# WIFI_Display.net
KiCad netlist of a schematic drawn in Altium Designer
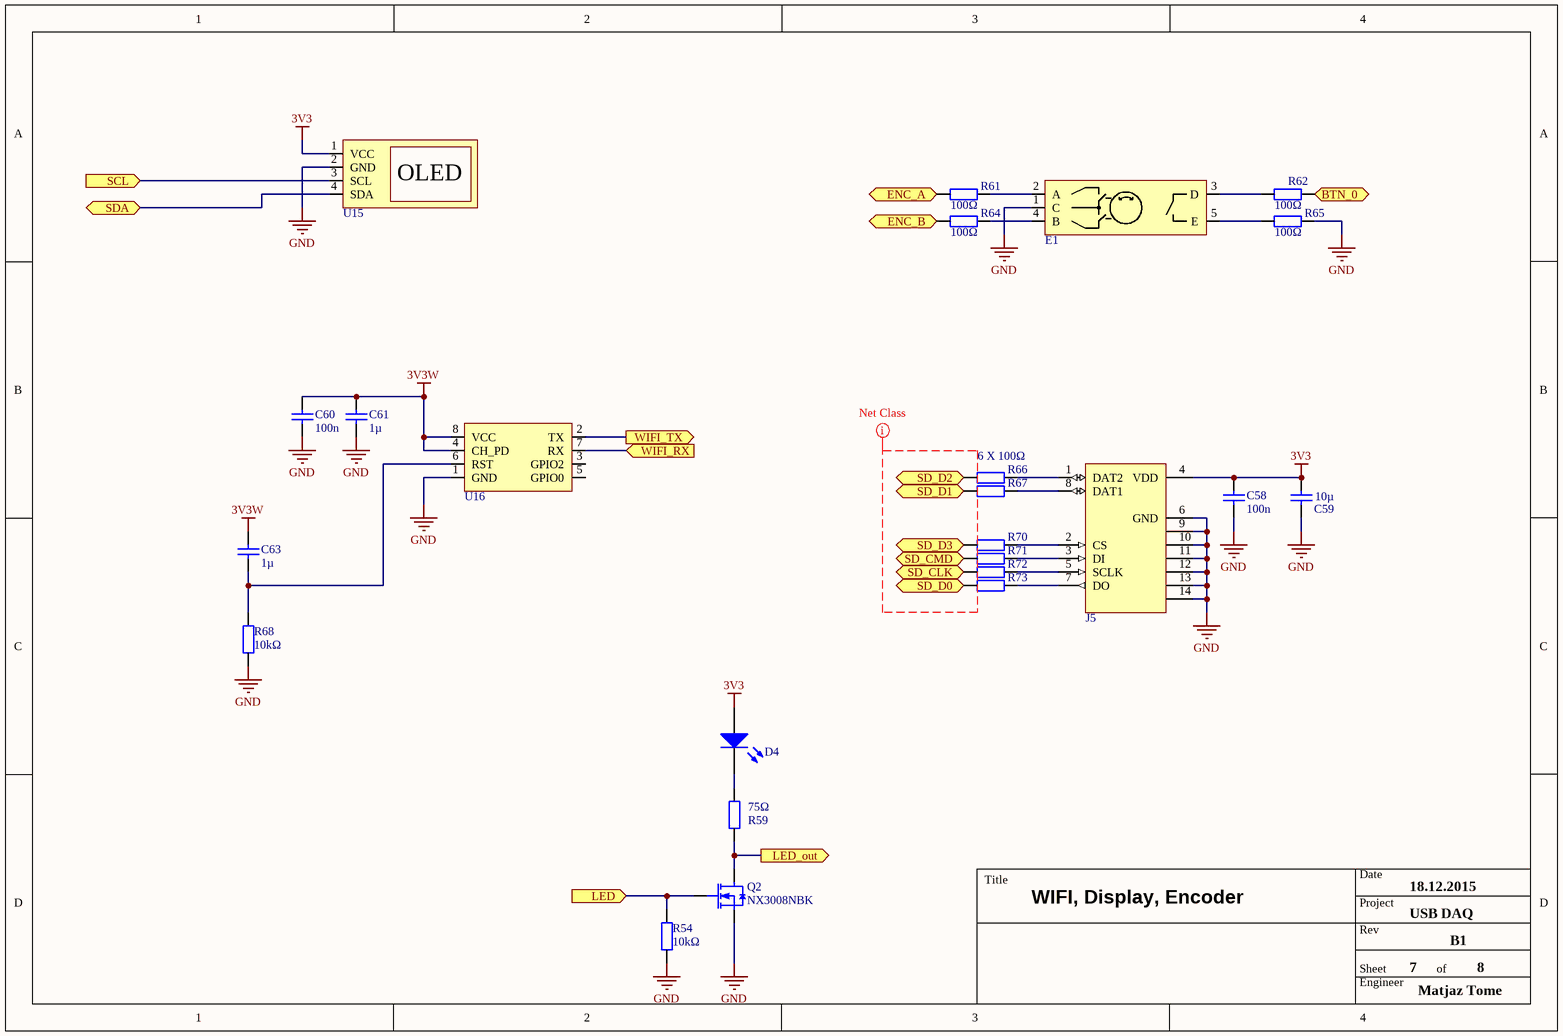
[diagram p0: WIFI_Display.SchDoc]

(export (version "E")
  (design (tool "Eeschema 10.0.6"))
  (components
    (comp (ref "C58")
      (value "100n")
      (footprint "0603C")
      (description "ceramic X7R SMD capacitor smd 0603 100nF 16V")
      (fields (field (name "PART NUMBER") "RSC0013") (field (name "MANUFACTURER") "Murata"))
      (libsource (lib "components") (part "Capacitor"))
    )
    (comp (ref "C59")
      (value "10µ")
      (footprint "0805C")
      (description "ceramic Y5V SMD capacitor smd 0805 10µF 6.3V")
      (fields (field (name "PART NUMBER") "VSC0001") (field (name "MANUFACTURER") "Multicomp"))
      (libsource (lib "components") (part "Capacitor"))
    )
    (comp (ref "C60")
      (value "100n")
      (footprint "0603C")
      (description "ceramic X7R SMD capacitor smd 0603 100nF 16V")
      (fields (field (name "PART NUMBER") "RSC0013") (field (name "MANUFACTURER") "Murata"))
      (libsource (lib "components") (part "Capacitor"))
    )
    (comp (ref "C61")
      (value "1µ")
      (footprint "0603C")
      (description "ceramic X5R SMD capacitor smd 0603 1µF 50V")
      (fields (field (name "PART NUMBER") "ZSC0003") (field (name "MANUFACTURER") "Murata"))
      (libsource (lib "components") (part "Capacitor"))
    )
    (comp (ref "C63")
      (value "1µ")
      (footprint "0603C")
      (description "ceramic X5R SMD capacitor smd 0603 1µF 50V")
      (fields (field (name "PART NUMBER") "ZSC0003") (field (name "MANUFACTURER") "Murata"))
      (libsource (lib "components") (part "Capacitor"))
    )
    (comp (ref "D4")
      (value "KPT-2012SGC")
      (footprint "LED0805")
      (description "Green led SMD 0805")
      (fields (field (name "PART NUMBER") "XXL0000") (field (name "MANUFACTURER") "Kingbright"))
      (libsource (lib "components") (part "LED"))
    )
    (comp (ref "E1")
      (value "EC12D")
      (footprint "EC12D")
      (description "Rotary encoder with push button")
      (fields (field (name "PART NUMBER") "XRE0000") (field (name "MANUFACTURER") "Alps"))
      (libsource (lib "components") (part "ENC1"))
    )
    (comp (ref "J5")
      (value "SD card")
      (footprint "MICRO_SD_AMPHENOL")
      (description "Micro SD card connector")
      (fields (field (name "PART NUMBER") "XMC0000") (field (name "MANUFACTURER") "Amphenol"))
      (libsource (lib "components") (part "MICRO_SD_1"))
    )
    (comp (ref "Q2")
      (value "NX3008NBK")
      (footprint "SOT23-3")
      (description "30V 0.4A N-mosfet")
      (fields (field (name "PART NUMBER") "XMN0003") (field (name "MANUFACTURER") "NXP"))
      (libsource (lib "components") (part "MOSFET_2"))
    )
    (comp (ref "R54")
      (value "10kΩ")
      (footprint "0603R")
      (description "resistor smd 0603 10kΩ 1% 0.1w")
      (fields (field (name "PART NUMBER") "YRS0016") (field (name "MANUFACTURER") "Vishay"))
      (libsource (lib "") (part "Resistor_1"))
    )
    (comp (ref "R59")
      (value "75Ω")
      (footprint "0603R")
      (description "resistor smd 0603 75Ω 5% 0.1w")
      (fields (field (name "PART NUMBER") "XRS0024") (field (name "MANUFACTURER") "Multicomp"))
      (libsource (lib "") (part "Resistor_1"))
    )
    (comp (ref "R61")
      (value "100Ω")
      (footprint "0603R")
      (description "resistor smd 0603 100Ω 5% 0.1w")
      (fields (field (name "PART NUMBER") "XRS0016") (field (name "MANUFACTURER") "Multicomp"))
      (libsource (lib "components") (part "Resistor"))
    )
    (comp (ref "R62")
      (value "100Ω")
      (footprint "0603R")
      (description "resistor smd 0603 100Ω 5% 0.1w")
      (fields (field (name "PART NUMBER") "XRS0016") (field (name "MANUFACTURER") "Multicomp"))
      (libsource (lib "components") (part "Resistor"))
    )
    (comp (ref "R64")
      (value "100Ω")
      (footprint "0603R")
      (description "resistor smd 0603 100Ω 5% 0.1w")
      (fields (field (name "PART NUMBER") "XRS0016") (field (name "MANUFACTURER") "Multicomp"))
      (libsource (lib "components") (part "Resistor"))
    )
    (comp (ref "R65")
      (value "100Ω")
      (footprint "0603R")
      (description "resistor smd 0603 100Ω 5% 0.1w")
      (fields (field (name "PART NUMBER") "XRS0016") (field (name "MANUFACTURER") "Multicomp"))
      (libsource (lib "components") (part "Resistor"))
    )
    (comp (ref "R66")
      (value "100Ω")
      (footprint "0603R")
      (description "resistor smd 0603 100Ω 5% 0.1w")
      (fields (field (name "PART NUMBER") "XRS0016") (field (name "MANUFACTURER") "Multicomp"))
      (libsource (lib "components") (part "Resistor"))
    )
    (comp (ref "R67")
      (value "100Ω")
      (footprint "0603R")
      (description "resistor smd 0603 100Ω 5% 0.1w")
      (fields (field (name "PART NUMBER") "XRS0016") (field (name "MANUFACTURER") "Multicomp"))
      (libsource (lib "components") (part "Resistor"))
    )
    (comp (ref "R68")
      (value "10kΩ")
      (footprint "0603R")
      (description "resistor smd 0603 10kΩ 1% 0.1w")
      (fields (field (name "PART NUMBER") "YRS0016") (field (name "MANUFACTURER") "Vishay"))
      (libsource (lib "") (part "Resistor_1"))
    )
    (comp (ref "R70")
      (value "100Ω")
      (footprint "0603R")
      (description "resistor smd 0603 100Ω 5% 0.1w")
      (fields (field (name "PART NUMBER") "XRS0016") (field (name "MANUFACTURER") "Multicomp"))
      (libsource (lib "components") (part "Resistor"))
    )
    (comp (ref "R71")
      (value "100Ω")
      (footprint "0603R")
      (description "resistor smd 0603 100Ω 5% 0.1w")
      (fields (field (name "PART NUMBER") "XRS0016") (field (name "MANUFACTURER") "Multicomp"))
      (libsource (lib "components") (part "Resistor"))
    )
    (comp (ref "R72")
      (value "100Ω")
      (footprint "0603R")
      (description "resistor smd 0603 100Ω 5% 0.1w")
      (fields (field (name "PART NUMBER") "XRS0016") (field (name "MANUFACTURER") "Multicomp"))
      (libsource (lib "components") (part "Resistor"))
    )
    (comp (ref "R73")
      (value "100Ω")
      (footprint "0603R")
      (description "resistor smd 0603 100Ω 5% 0.1w")
      (fields (field (name "PART NUMBER") "XRS0016") (field (name "MANUFACTURER") "Multicomp"))
      (libsource (lib "components") (part "Resistor"))
    )
    (comp (ref "U15")
      (value "SSD1306")
      (footprint "OLED1")
      (description "Oled display module")
      (fields (field (name "PART NUMBER") "OLM0000"))
      (libsource (lib "components") (part "OLED_SSD1306"))
    )
    (comp (ref "U16")
      (value "ESP-01")
      (footprint "ESP-01")
      (description "WIFI module")
      (fields (field (name "PART NUMBER") "XWM0000"))
      (libsource (lib "components") (part "ESP-01"))
    )
  )
  (nets
    (net (code "1") (name "/BTN_0") (class "Default")
      (node (ref "R62") (pin "2") (pinfunction "2_2") (pintype "passive"))
    )
    (net (code "2") (name "/ENC_A") (class "Default")
      (node (ref "R61") (pin "1") (pinfunction "1_1") (pintype "passive"))
    )
    (net (code "3") (name "/ENC_B") (class "Default")
      (node (ref "R64") (pin "1") (pinfunction "1_1") (pintype "passive"))
    )
    (net (code "4") (name "/LED") (class "Default")
      (node (ref "Q2") (pin "1") (pinfunction "G_1") (pintype "passive"))
      (node (ref "R54") (pin "2") (pinfunction "2_2") (pintype "passive"))
    )
    (net (code "5") (name "/LED_out") (class "Default")
      (node (ref "Q2") (pin "3") (pinfunction "D_3") (pintype "passive"))
      (node (ref "R59") (pin "1") (pinfunction "1_1") (pintype "passive"))
    )
    (net (code "6") (name "/SCL") (class "Default")
      (node (ref "U15") (pin "3") (pinfunction "SCL_3") (pintype "passive"))
    )
    (net (code "7") (name "/SDA") (class "Default")
      (node (ref "U15") (pin "4") (pinfunction "SDA_4") (pintype "passive"))
    )
    (net (code "8") (name "/SD_CLK") (class "Default")
      (node (ref "R72") (pin "1") (pinfunction "1_1") (pintype "passive"))
    )
    (net (code "9") (name "/SD_CMD") (class "Default")
      (node (ref "R71") (pin "1") (pinfunction "1_1") (pintype "passive"))
    )
    (net (code "10") (name "/SD_D0") (class "Default")
      (node (ref "R73") (pin "1") (pinfunction "1_1") (pintype "passive"))
    )
    (net (code "11") (name "/SD_D1") (class "Default")
      (node (ref "R67") (pin "1") (pinfunction "1_1") (pintype "passive"))
    )
    (net (code "12") (name "/SD_D2") (class "Default")
      (node (ref "R66") (pin "1") (pinfunction "1_1") (pintype "passive"))
    )
    (net (code "13") (name "/SD_D3") (class "Default")
      (node (ref "R70") (pin "1") (pinfunction "1_1") (pintype "passive"))
    )
    (net (code "14") (name "/WIFI_RX") (class "Default")
      (node (ref "U16") (pin "7") (pinfunction "RX_7") (pintype "passive"))
    )
    (net (code "15") (name "/WIFI_TX") (class "Default")
      (node (ref "U16") (pin "2") (pinfunction "TX_2") (pintype "passive"))
    )
    (net (code "16") (name "3V3") (class "Default")
      (node (ref "C58") (pin "1") (pinfunction "1_1") (pintype "passive"))
      (node (ref "C59") (pin "2") (pinfunction "2_2") (pintype "passive"))
      (node (ref "D4") (pin "A") (pinfunction "A_A") (pintype "passive"))
      (node (ref "J5") (pin "4") (pinfunction "VDD_4") (pintype "power_in"))
      (node (ref "U15") (pin "1") (pinfunction "VCC_1") (pintype "passive"))
    )
    (net (code "17") (name "3V3W") (class "Default")
      (node (ref "C60") (pin "1") (pinfunction "1_1") (pintype "passive"))
      (node (ref "C61") (pin "2") (pinfunction "2_2") (pintype "passive"))
      (node (ref "C63") (pin "2") (pinfunction "2_2") (pintype "passive"))
      (node (ref "U16") (pin "4") (pinfunction "CH_PD_4") (pintype "passive"))
      (node (ref "U16") (pin "8") (pinfunction "VCC_8") (pintype "passive"))
    )
    (net (code "18") (name "GND") (class "Default")
      (node (ref "C58") (pin "2") (pinfunction "2_2") (pintype "passive"))
      (node (ref "C59") (pin "1") (pinfunction "1_1") (pintype "passive"))
      (node (ref "C60") (pin "2") (pinfunction "2_2") (pintype "passive"))
      (node (ref "C61") (pin "1") (pinfunction "1_1") (pintype "passive"))
      (node (ref "E1") (pin "1") (pinfunction "C_1") (pintype "passive"))
      (node (ref "J5") (pin "10") (pinfunction "10_10") (pintype "passive"))
      (node (ref "J5") (pin "11") (pinfunction "11_11") (pintype "passive"))
      (node (ref "J5") (pin "12") (pinfunction "12_12") (pintype "passive"))
      (node (ref "J5") (pin "13") (pinfunction "13_13") (pintype "passive"))
      (node (ref "J5") (pin "14") (pinfunction "14_14") (pintype "passive"))
      (node (ref "J5") (pin "6") (pinfunction "GND_6") (pintype "power_in"))
      (node (ref "J5") (pin "9") (pinfunction "9_9") (pintype "passive"))
      (node (ref "Q2") (pin "2") (pinfunction "S_2") (pintype "passive"))
      (node (ref "R54") (pin "1") (pinfunction "1_1") (pintype "passive"))
      (node (ref "R65") (pin "2") (pinfunction "2_2") (pintype "passive"))
      (node (ref "R68") (pin "1") (pinfunction "1_1") (pintype "passive"))
      (node (ref "U15") (pin "2") (pinfunction "GND_2") (pintype "passive"))
      (node (ref "U16") (pin "1") (pinfunction "GND_1") (pintype "passive"))
    )
    (net (code "19") (name "Net-(D4-PadK)") (class "Default")
      (node (ref "D4") (pin "K") (pinfunction "K_K") (pintype "passive"))
      (node (ref "R59") (pin "2") (pinfunction "2_2") (pintype "passive"))
    )
    (net (code "20") (name "Net-(E1-A)") (class "Default")
      (node (ref "E1") (pin "2") (pinfunction "A_2") (pintype "passive"))
      (node (ref "R61") (pin "2") (pinfunction "2_2") (pintype "passive"))
    )
    (net (code "21") (name "Net-(E1-B)") (class "Default")
      (node (ref "E1") (pin "4") (pinfunction "B_4") (pintype "passive"))
      (node (ref "R64") (pin "2") (pinfunction "2_2") (pintype "passive"))
    )
    (net (code "22") (name "Net-(E1-D)") (class "Default")
      (node (ref "E1") (pin "3") (pinfunction "D_3") (pintype "passive"))
      (node (ref "R62") (pin "1") (pinfunction "1_1") (pintype "passive"))
    )
    (net (code "23") (name "Net-(E1-E)") (class "Default")
      (node (ref "E1") (pin "5") (pinfunction "E_5") (pintype "passive"))
      (node (ref "R65") (pin "1") (pinfunction "1_1") (pintype "passive"))
    )
    (net (code "24") (name "Net-(J5-CS)") (class "Default")
      (node (ref "J5") (pin "2") (pinfunction "CS_2") (pintype "input"))
      (node (ref "R70") (pin "2") (pinfunction "2_2") (pintype "passive"))
    )
    (net (code "25") (name "Net-(J5-DAT1)") (class "Default")
      (node (ref "J5") (pin "8") (pinfunction "DAT1_8") (pintype "bidirectional"))
      (node (ref "R67") (pin "2") (pinfunction "2_2") (pintype "passive"))
    )
    (net (code "26") (name "Net-(J5-DAT2)") (class "Default")
      (node (ref "J5") (pin "1") (pinfunction "DAT2_1") (pintype "bidirectional"))
      (node (ref "R66") (pin "2") (pinfunction "2_2") (pintype "passive"))
    )
    (net (code "27") (name "Net-(J5-DI)") (class "Default")
      (node (ref "J5") (pin "3") (pinfunction "DI_3") (pintype "input"))
      (node (ref "R71") (pin "2") (pinfunction "2_2") (pintype "passive"))
    )
    (net (code "28") (name "Net-(J5-DO)") (class "Default")
      (node (ref "J5") (pin "7") (pinfunction "DO_7") (pintype "output"))
      (node (ref "R73") (pin "2") (pinfunction "2_2") (pintype "passive"))
    )
    (net (code "29") (name "Net-(J5-SCLK)") (class "Default")
      (node (ref "J5") (pin "5") (pinfunction "SCLK_5") (pintype "input"))
      (node (ref "R72") (pin "2") (pinfunction "2_2") (pintype "passive"))
    )
    (net (code "30") (name "Net-(U16-RST)") (class "Default")
      (node (ref "C63") (pin "1") (pinfunction "1_1") (pintype "passive"))
      (node (ref "R68") (pin "2") (pinfunction "2_2") (pintype "passive"))
      (node (ref "U16") (pin "6") (pinfunction "RST_6") (pintype "passive"))
    )
    (net (code "31") (name "unconnected-(U16-GPIO0-Pad5)") (class "Default")
      (node (ref "U16") (pin "5") (pinfunction "GPIO0_5") (pintype "passive"))
    )
    (net (code "32") (name "unconnected-(U16-GPIO2-Pad3)") (class "Default")
      (node (ref "U16") (pin "3") (pinfunction "GPIO2_3") (pintype "passive"))
    )
  )
)
